# Daughter_Board.net
KiCad netlist of a schematic drawn in EAGLE
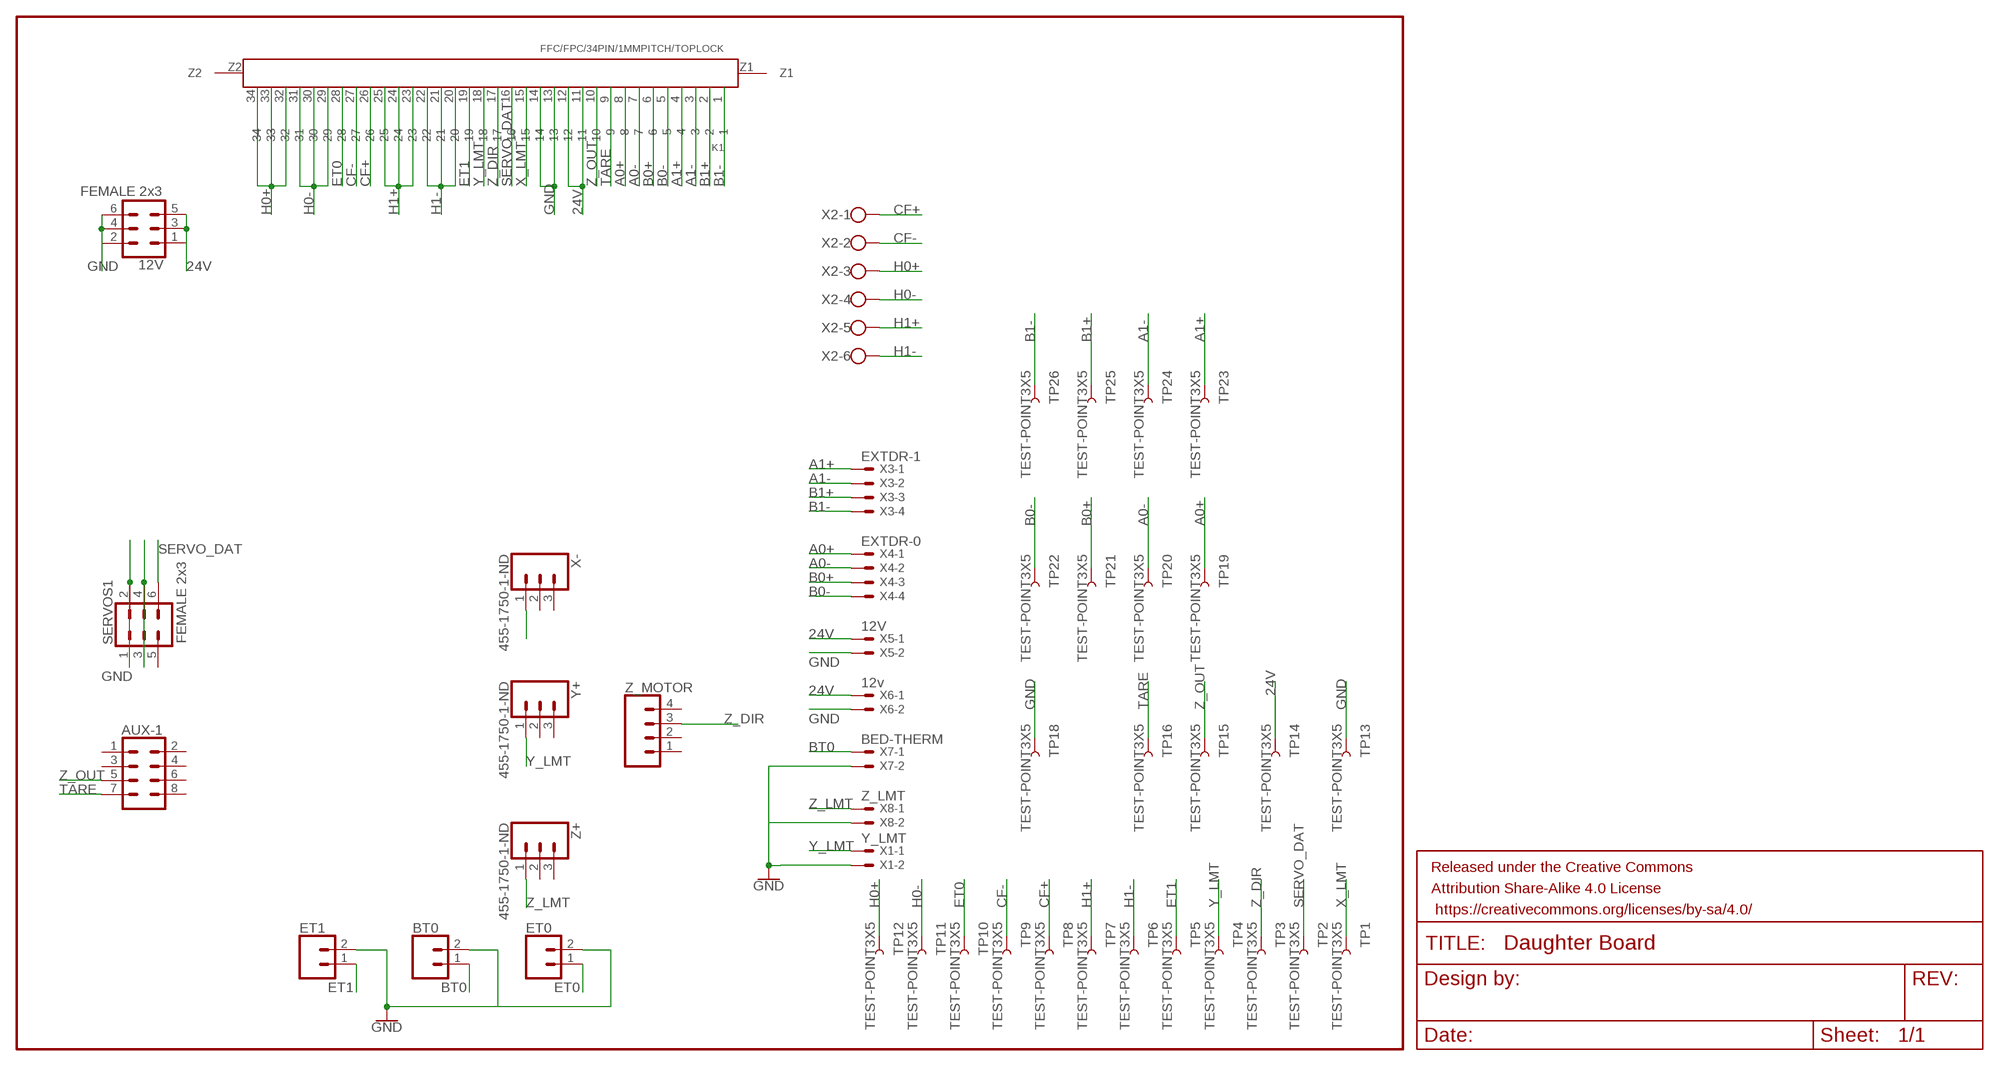
[diagram p0: schematic, sheet 1]

(export (version "E")
  (design (tool "Eeschema 10.0.6"))
  (components
    (comp (ref "12V")
      (value "FEMALE 2x3")
      (footprint "eagle-import:2X3")
      (libsource (lib "eagle-import") (part "CONN_03X2FEMALE"))
    )
    (comp (ref "AUX-1")
      (value "CONN_04X2")
      (footprint "eagle-import:2X4")
      (libsource (lib "eagle-import") (part "CONN_04X2"))
    )
    (comp (ref "BT0")
      (value "CONN_02")
      (footprint "eagle-import:1X02")
      (libsource (lib "eagle-import") (part "CONN_02"))
    )
    (comp (ref "ET0")
      (value "CONN_02")
      (footprint "eagle-import:1X02")
      (libsource (lib "eagle-import") (part "CONN_02"))
    )
    (comp (ref "ET1")
      (value "CONN_02")
      (footprint "eagle-import:1X02")
      (libsource (lib "eagle-import") (part "CONN_02"))
    )
    (comp (ref "FRAME1")
      (value "FRAME-LETTERNO_PACKAGE")
      (footprint "eagle-import:DUMMY")
      (fields (field (name "DESIGNER") "Nobody"))
      (libsource (lib "eagle-import") (part "FRAME-LETTERNO_PACKAGE"))
    )
    (comp (ref "K1")
      (value "FFC/FPC/34PIN/1MMPITCH/TOPLOCK")
      (footprint "eagle-import:34PIN_1MMPITCH_FFC_FPC")
      (libsource (lib "eagle-import") (part "FFC/FPC/34PIN/1MMPITCH/TOPLOCK"))
    )
    (comp (ref "SERVOS1")
      (value "FEMALE 2x3")
      (footprint "eagle-import:2X3")
      (libsource (lib "eagle-import") (part "CONN_03X2FEMALE"))
    )
    (comp (ref "TP1")
      (value "TEST-POINT3X5")
      (footprint "eagle-import:PAD.03X.05")
      (libsource (lib "eagle-import") (part "TEST-POINT3X5"))
    )
    (comp (ref "TP2")
      (value "TEST-POINT3X5")
      (footprint "eagle-import:PAD.03X.05")
      (libsource (lib "eagle-import") (part "TEST-POINT3X5"))
    )
    (comp (ref "TP3")
      (value "TEST-POINT3X5")
      (footprint "eagle-import:PAD.03X.05")
      (libsource (lib "eagle-import") (part "TEST-POINT3X5"))
    )
    (comp (ref "TP4")
      (value "TEST-POINT3X5")
      (footprint "eagle-import:PAD.03X.05")
      (libsource (lib "eagle-import") (part "TEST-POINT3X5"))
    )
    (comp (ref "TP5")
      (value "TEST-POINT3X5")
      (footprint "eagle-import:PAD.03X.05")
      (libsource (lib "eagle-import") (part "TEST-POINT3X5"))
    )
    (comp (ref "TP6")
      (value "TEST-POINT3X5")
      (footprint "eagle-import:PAD.03X.05")
      (libsource (lib "eagle-import") (part "TEST-POINT3X5"))
    )
    (comp (ref "TP7")
      (value "TEST-POINT3X5")
      (footprint "eagle-import:PAD.03X.05")
      (libsource (lib "eagle-import") (part "TEST-POINT3X5"))
    )
    (comp (ref "TP8")
      (value "TEST-POINT3X5")
      (footprint "eagle-import:PAD.03X.05")
      (libsource (lib "eagle-import") (part "TEST-POINT3X5"))
    )
    (comp (ref "TP9")
      (value "TEST-POINT3X5")
      (footprint "eagle-import:PAD.03X.05")
      (libsource (lib "eagle-import") (part "TEST-POINT3X5"))
    )
    (comp (ref "TP10")
      (value "TEST-POINT3X5")
      (footprint "eagle-import:PAD.03X.05")
      (libsource (lib "eagle-import") (part "TEST-POINT3X5"))
    )
    (comp (ref "TP11")
      (value "TEST-POINT3X5")
      (footprint "eagle-import:PAD.03X.05")
      (libsource (lib "eagle-import") (part "TEST-POINT3X5"))
    )
    (comp (ref "TP12")
      (value "TEST-POINT3X5")
      (footprint "eagle-import:PAD.03X.05")
      (libsource (lib "eagle-import") (part "TEST-POINT3X5"))
    )
    (comp (ref "TP13")
      (value "TEST-POINT3X5")
      (footprint "eagle-import:PAD.03X.05")
      (libsource (lib "eagle-import") (part "TEST-POINT3X5"))
    )
    (comp (ref "TP14")
      (value "TEST-POINT3X5")
      (footprint "eagle-import:PAD.03X.05")
      (libsource (lib "eagle-import") (part "TEST-POINT3X5"))
    )
    (comp (ref "TP15")
      (value "TEST-POINT3X5")
      (footprint "eagle-import:PAD.03X.05")
      (libsource (lib "eagle-import") (part "TEST-POINT3X5"))
    )
    (comp (ref "TP16")
      (value "TEST-POINT3X5")
      (footprint "eagle-import:PAD.03X.05")
      (libsource (lib "eagle-import") (part "TEST-POINT3X5"))
    )
    (comp (ref "TP18")
      (value "TEST-POINT3X5")
      (footprint "eagle-import:PAD.03X.05")
      (libsource (lib "eagle-import") (part "TEST-POINT3X5"))
    )
    (comp (ref "TP19")
      (value "TEST-POINT3X5")
      (footprint "eagle-import:PAD.03X.05")
      (libsource (lib "eagle-import") (part "TEST-POINT3X5"))
    )
    (comp (ref "TP20")
      (value "TEST-POINT3X5")
      (footprint "eagle-import:PAD.03X.05")
      (libsource (lib "eagle-import") (part "TEST-POINT3X5"))
    )
    (comp (ref "TP21")
      (value "TEST-POINT3X5")
      (footprint "eagle-import:PAD.03X.05")
      (libsource (lib "eagle-import") (part "TEST-POINT3X5"))
    )
    (comp (ref "TP22")
      (value "TEST-POINT3X5")
      (footprint "eagle-import:PAD.03X.05")
      (libsource (lib "eagle-import") (part "TEST-POINT3X5"))
    )
    (comp (ref "TP23")
      (value "TEST-POINT3X5")
      (footprint "eagle-import:PAD.03X.05")
      (libsource (lib "eagle-import") (part "TEST-POINT3X5"))
    )
    (comp (ref "TP24")
      (value "TEST-POINT3X5")
      (footprint "eagle-import:PAD.03X.05")
      (libsource (lib "eagle-import") (part "TEST-POINT3X5"))
    )
    (comp (ref "TP25")
      (value "TEST-POINT3X5")
      (footprint "eagle-import:PAD.03X.05")
      (libsource (lib "eagle-import") (part "TEST-POINT3X5"))
    )
    (comp (ref "TP26")
      (value "TEST-POINT3X5")
      (footprint "eagle-import:PAD.03X.05")
      (libsource (lib "eagle-import") (part "TEST-POINT3X5"))
    )
    (comp (ref "X-")
      (value "455-1750-1-ND")
      (footprint "eagle-import:1X03")
      (libsource (lib "eagle-import") (part "CONN_03"))
    )
    (comp (ref "X1")
      (value "Y_LMT")
      (footprint "eagle-import:JST-XH-02-PACKAGE-LONG-PAD")
      (libsource (lib "eagle-import") (part "JST-XH-02-PIN-LONG-PAD"))
    )
    (comp (ref "X2")
      (value "W237-6")
      (footprint "eagle-import:W237-6")
      (libsource (lib "eagle-import") (part "W237-6"))
    )
    (comp (ref "X3")
      (value "EXTDR-1")
      (footprint "eagle-import:JST-XH-04-PACKAGE-LONG-PAD")
      (libsource (lib "eagle-import") (part "JST-XH-04-PIN-LONG-PAD"))
    )
    (comp (ref "X4")
      (value "EXTDR-0")
      (footprint "eagle-import:JST-XH-04-PACKAGE-LONG-PAD")
      (libsource (lib "eagle-import") (part "JST-XH-04-PIN-LONG-PAD"))
    )
    (comp (ref "X5")
      (value "12V")
      (footprint "eagle-import:JST-XH-02-PACKAGE-LONG-PAD")
      (libsource (lib "eagle-import") (part "JST-XH-02-PIN-LONG-PAD"))
    )
    (comp (ref "X6")
      (value "12v")
      (footprint "eagle-import:JST-XH-02-PACKAGE-LONG-PAD")
      (libsource (lib "eagle-import") (part "JST-XH-02-PIN-LONG-PAD"))
    )
    (comp (ref "X7")
      (value "BED-THERM")
      (footprint "eagle-import:JST-XH-02-PACKAGE-LONG-PAD")
      (libsource (lib "eagle-import") (part "JST-XH-02-PIN-LONG-PAD"))
    )
    (comp (ref "X8")
      (value "Z_LMT")
      (footprint "eagle-import:JST-XH-02-PACKAGE-LONG-PAD")
      (libsource (lib "eagle-import") (part "JST-XH-02-PIN-LONG-PAD"))
    )
    (comp (ref "Y+")
      (value "455-1750-1-ND")
      (footprint "eagle-import:1X03")
      (libsource (lib "eagle-import") (part "CONN_03"))
    )
    (comp (ref "Z+")
      (value "455-1750-1-ND")
      (footprint "eagle-import:1X03")
      (libsource (lib "eagle-import") (part "CONN_03"))
    )
    (comp (ref "Z_MOTOR")
      (value "CONN_04")
      (footprint "eagle-import:1X04")
      (libsource (lib "eagle-import") (part "CONN_04"))
    )
  )
  (nets
    (net (code "1") (name "/24V") (class "Default")
      (node (ref "12V") (pin "1") (pinfunction "1_1") (pintype "bidirectional"))
      (node (ref "12V") (pin "3") (pinfunction "3_3") (pintype "bidirectional"))
      (node (ref "12V") (pin "5") (pinfunction "5_5") (pintype "bidirectional"))
      (node (ref "K1") (pin "11") (pinfunction "11_11") (pintype "bidirectional"))
      (node (ref "K1") (pin "12") (pinfunction "12_12") (pintype "bidirectional"))
      (node (ref "TP14") (pin "P$1") (pinfunction "1_P$1") (pintype "bidirectional"))
      (node (ref "X5") (pin "1") (pinfunction "S_1") (pintype "passive"))
      (node (ref "X6") (pin "1") (pinfunction "S_1") (pintype "passive"))
    )
    (net (code "2") (name "/A0+") (class "Default")
      (node (ref "K1") (pin "8") (pinfunction "8_8") (pintype "bidirectional"))
      (node (ref "TP19") (pin "P$1") (pinfunction "1_P$1") (pintype "bidirectional"))
      (node (ref "X4") (pin "1") (pinfunction "S_1") (pintype "passive"))
    )
    (net (code "3") (name "/A0-") (class "Default")
      (node (ref "K1") (pin "7") (pinfunction "7_7") (pintype "bidirectional"))
      (node (ref "TP20") (pin "P$1") (pinfunction "1_P$1") (pintype "bidirectional"))
      (node (ref "X4") (pin "2") (pinfunction "S_2") (pintype "passive"))
    )
    (net (code "4") (name "/A1+") (class "Default")
      (node (ref "K1") (pin "4") (pinfunction "4_4") (pintype "bidirectional"))
      (node (ref "TP23") (pin "P$1") (pinfunction "1_P$1") (pintype "bidirectional"))
      (node (ref "X3") (pin "1") (pinfunction "S_1") (pintype "passive"))
    )
    (net (code "5") (name "/A1-") (class "Default")
      (node (ref "K1") (pin "3") (pinfunction "3_3") (pintype "bidirectional"))
      (node (ref "TP24") (pin "P$1") (pinfunction "1_P$1") (pintype "bidirectional"))
      (node (ref "X3") (pin "2") (pinfunction "S_2") (pintype "passive"))
    )
    (net (code "6") (name "/B0+") (class "Default")
      (node (ref "K1") (pin "6") (pinfunction "6_6") (pintype "bidirectional"))
      (node (ref "TP21") (pin "P$1") (pinfunction "1_P$1") (pintype "bidirectional"))
      (node (ref "X4") (pin "3") (pinfunction "S_3") (pintype "passive"))
    )
    (net (code "7") (name "/B0-") (class "Default")
      (node (ref "K1") (pin "5") (pinfunction "5_5") (pintype "bidirectional"))
      (node (ref "TP22") (pin "P$1") (pinfunction "1_P$1") (pintype "bidirectional"))
      (node (ref "X4") (pin "4") (pinfunction "S_4") (pintype "passive"))
    )
    (net (code "8") (name "/B1+") (class "Default")
      (node (ref "K1") (pin "2") (pinfunction "2_2") (pintype "bidirectional"))
      (node (ref "TP25") (pin "P$1") (pinfunction "1_P$1") (pintype "bidirectional"))
      (node (ref "X3") (pin "3") (pinfunction "S_3") (pintype "passive"))
    )
    (net (code "9") (name "/B1-") (class "Default")
      (node (ref "K1") (pin "1") (pinfunction "1_1") (pintype "bidirectional"))
      (node (ref "TP26") (pin "P$1") (pinfunction "1_P$1") (pintype "bidirectional"))
      (node (ref "X3") (pin "4") (pinfunction "S_4") (pintype "passive"))
    )
    (net (code "10") (name "/BT0") (class "Default")
      (node (ref "BT0") (pin "1") (pinfunction "1_1") (pintype "passive"))
      (node (ref "X7") (pin "1") (pinfunction "S_1") (pintype "passive"))
    )
    (net (code "11") (name "/CF+") (class "Default")
      (node (ref "K1") (pin "26") (pinfunction "26_26") (pintype "bidirectional"))
      (node (ref "TP8") (pin "P$1") (pinfunction "1_P$1") (pintype "bidirectional"))
      (node (ref "X2") (pin "1") (pinfunction "KL_1") (pintype "passive"))
    )
    (net (code "12") (name "/CF-") (class "Default")
      (node (ref "K1") (pin "27") (pinfunction "27_27") (pintype "bidirectional"))
      (node (ref "TP9") (pin "P$1") (pinfunction "1_P$1") (pintype "bidirectional"))
      (node (ref "X2") (pin "2") (pinfunction "KL_2") (pintype "passive"))
    )
    (net (code "13") (name "/ET0") (class "Default")
      (node (ref "ET0") (pin "1") (pinfunction "1_1") (pintype "passive"))
      (node (ref "K1") (pin "28") (pinfunction "28_28") (pintype "bidirectional"))
      (node (ref "TP10") (pin "P$1") (pinfunction "1_P$1") (pintype "bidirectional"))
    )
    (net (code "14") (name "/ET1") (class "Default")
      (node (ref "ET1") (pin "1") (pinfunction "1_1") (pintype "passive"))
      (node (ref "K1") (pin "19") (pinfunction "19_19") (pintype "bidirectional"))
      (node (ref "TP5") (pin "P$1") (pinfunction "1_P$1") (pintype "bidirectional"))
    )
    (net (code "15") (name "/H0+") (class "Default")
      (node (ref "K1") (pin "32") (pinfunction "32_32") (pintype "bidirectional"))
      (node (ref "K1") (pin "33") (pinfunction "33_33") (pintype "bidirectional"))
      (node (ref "K1") (pin "34") (pinfunction "34_34") (pintype "bidirectional"))
      (node (ref "TP12") (pin "P$1") (pinfunction "1_P$1") (pintype "bidirectional"))
      (node (ref "X2") (pin "3") (pinfunction "KL_3") (pintype "passive"))
    )
    (net (code "16") (name "/H0-") (class "Default")
      (node (ref "K1") (pin "29") (pinfunction "29_29") (pintype "bidirectional"))
      (node (ref "K1") (pin "30") (pinfunction "30_30") (pintype "bidirectional"))
      (node (ref "K1") (pin "31") (pinfunction "31_31") (pintype "bidirectional"))
      (node (ref "TP11") (pin "P$1") (pinfunction "1_P$1") (pintype "bidirectional"))
      (node (ref "X2") (pin "4") (pinfunction "KL_4") (pintype "passive"))
    )
    (net (code "17") (name "/H1+") (class "Default")
      (node (ref "K1") (pin "23") (pinfunction "23_23") (pintype "bidirectional"))
      (node (ref "K1") (pin "24") (pinfunction "24_24") (pintype "bidirectional"))
      (node (ref "K1") (pin "25") (pinfunction "25_25") (pintype "bidirectional"))
      (node (ref "TP7") (pin "P$1") (pinfunction "1_P$1") (pintype "bidirectional"))
      (node (ref "X2") (pin "5") (pinfunction "KL_5") (pintype "passive"))
    )
    (net (code "18") (name "/H1-") (class "Default")
      (node (ref "K1") (pin "20") (pinfunction "20_20") (pintype "bidirectional"))
      (node (ref "K1") (pin "21") (pinfunction "21_21") (pintype "bidirectional"))
      (node (ref "K1") (pin "22") (pinfunction "22_22") (pintype "bidirectional"))
      (node (ref "TP6") (pin "P$1") (pinfunction "1_P$1") (pintype "bidirectional"))
      (node (ref "X2") (pin "6") (pinfunction "KL_6") (pintype "passive"))
    )
    (net (code "19") (name "/SERVO_DAT") (class "Default")
      (node (ref "K1") (pin "16") (pinfunction "16_16") (pintype "bidirectional"))
      (node (ref "SERVOS1") (pin "6") (pinfunction "6_6") (pintype "bidirectional"))
      (node (ref "TP2") (pin "P$1") (pinfunction "1_P$1") (pintype "bidirectional"))
    )
    (net (code "20") (name "/TARE") (class "Default")
      (node (ref "AUX-1") (pin "7") (pinfunction "7_7") (pintype "passive"))
      (node (ref "K1") (pin "9") (pinfunction "9_9") (pintype "bidirectional"))
      (node (ref "TP16") (pin "P$1") (pinfunction "1_P$1") (pintype "bidirectional"))
    )
    (net (code "21") (name "/X_LMT") (class "Default")
      (node (ref "K1") (pin "15") (pinfunction "15_15") (pintype "bidirectional"))
      (node (ref "TP1") (pin "P$1") (pinfunction "1_P$1") (pintype "bidirectional"))
      (node (ref "X-") (pin "1") (pinfunction "1_1") (pintype "passive"))
    )
    (net (code "22") (name "/Y_LMT") (class "Default")
      (node (ref "K1") (pin "18") (pinfunction "18_18") (pintype "bidirectional"))
      (node (ref "TP4") (pin "P$1") (pinfunction "1_P$1") (pintype "bidirectional"))
      (node (ref "X1") (pin "1") (pinfunction "S_1") (pintype "passive"))
      (node (ref "Y+") (pin "1") (pinfunction "1_1") (pintype "passive"))
    )
    (net (code "23") (name "/Z_DIR") (class "Default")
      (node (ref "K1") (pin "17") (pinfunction "17_17") (pintype "bidirectional"))
      (node (ref "TP3") (pin "P$1") (pinfunction "1_P$1") (pintype "bidirectional"))
      (node (ref "Z_MOTOR") (pin "3") (pinfunction "3_3") (pintype "passive"))
    )
    (net (code "24") (name "/Z_LMT") (class "Default")
      (node (ref "X8") (pin "1") (pinfunction "S_1") (pintype "passive"))
      (node (ref "Z+") (pin "1") (pinfunction "1_1") (pintype "passive"))
    )
    (net (code "25") (name "/Z_OUT") (class "Default")
      (node (ref "AUX-1") (pin "5") (pinfunction "5_5") (pintype "passive"))
      (node (ref "K1") (pin "10") (pinfunction "10_10") (pintype "bidirectional"))
      (node (ref "TP15") (pin "P$1") (pinfunction "1_P$1") (pintype "bidirectional"))
    )
    (net (code "26") (name "GND") (class "Default")
      (node (ref "12V") (pin "2") (pinfunction "2_2") (pintype "bidirectional"))
      (node (ref "12V") (pin "4") (pinfunction "4_4") (pintype "bidirectional"))
      (node (ref "12V") (pin "6") (pinfunction "6_6") (pintype "bidirectional"))
      (node (ref "BT0") (pin "2") (pinfunction "2_2") (pintype "passive"))
      (node (ref "ET0") (pin "2") (pinfunction "2_2") (pintype "passive"))
      (node (ref "ET1") (pin "2") (pinfunction "2_2") (pintype "passive"))
      (node (ref "K1") (pin "13") (pinfunction "13_13") (pintype "bidirectional"))
      (node (ref "K1") (pin "14") (pinfunction "14_14") (pintype "bidirectional"))
      (node (ref "SERVOS1") (pin "1") (pinfunction "1_1") (pintype "bidirectional"))
      (node (ref "SERVOS1") (pin "2") (pinfunction "2_2") (pintype "bidirectional"))
      (node (ref "TP13") (pin "P$1") (pinfunction "1_P$1") (pintype "bidirectional"))
      (node (ref "TP18") (pin "P$1") (pinfunction "1_P$1") (pintype "bidirectional"))
      (node (ref "X1") (pin "2") (pinfunction "S_2") (pintype "passive"))
      (node (ref "X5") (pin "2") (pinfunction "S_2") (pintype "passive"))
      (node (ref "X6") (pin "2") (pinfunction "S_2") (pintype "passive"))
      (node (ref "X7") (pin "2") (pinfunction "S_2") (pintype "passive"))
      (node (ref "X8") (pin "2") (pinfunction "S_2") (pintype "passive"))
    )
    (net (code "27") (name "Net-(SERVOS1-Pad3)") (class "Default")
      (node (ref "SERVOS1") (pin "3") (pinfunction "3_3") (pintype "bidirectional"))
      (node (ref "SERVOS1") (pin "4") (pinfunction "4_4") (pintype "bidirectional"))
    )
    (net (code "28") (name "unconnected-(AUX-1-Pad1)") (class "Default")
      (node (ref "AUX-1") (pin "1") (pinfunction "1_1") (pintype "passive"))
    )
    (net (code "29") (name "unconnected-(AUX-1-Pad2)") (class "Default")
      (node (ref "AUX-1") (pin "2") (pinfunction "2_2") (pintype "passive"))
    )
    (net (code "30") (name "unconnected-(AUX-1-Pad3)") (class "Default")
      (node (ref "AUX-1") (pin "3") (pinfunction "3_3") (pintype "passive"))
    )
    (net (code "31") (name "unconnected-(AUX-1-Pad4)") (class "Default")
      (node (ref "AUX-1") (pin "4") (pinfunction "4_4") (pintype "passive"))
    )
    (net (code "32") (name "unconnected-(AUX-1-Pad6)") (class "Default")
      (node (ref "AUX-1") (pin "6") (pinfunction "6_6") (pintype "passive"))
    )
    (net (code "33") (name "unconnected-(AUX-1-Pad8)") (class "Default")
      (node (ref "AUX-1") (pin "8") (pinfunction "8_8") (pintype "passive"))
    )
    (net (code "34") (name "unconnected-(K1-PadZ1)") (class "Default")
      (node (ref "K1") (pin "Z1") (pinfunction "Z1_Z1") (pintype "bidirectional"))
    )
    (net (code "35") (name "unconnected-(K1-PadZ2)") (class "Default")
      (node (ref "K1") (pin "Z2") (pinfunction "Z2_Z2") (pintype "bidirectional"))
    )
    (net (code "36") (name "unconnected-(SERVOS1-Pad5)") (class "Default")
      (node (ref "SERVOS1") (pin "5") (pinfunction "5_5") (pintype "bidirectional"))
    )
    (net (code "37") (name "unconnected-(X--Pad2)") (class "Default")
      (node (ref "X-") (pin "2") (pinfunction "2_2") (pintype "passive"))
    )
    (net (code "38") (name "unconnected-(X--Pad3)") (class "Default")
      (node (ref "X-") (pin "3") (pinfunction "3_3") (pintype "passive"))
    )
    (net (code "39") (name "unconnected-(Y+-Pad2)") (class "Default")
      (node (ref "Y+") (pin "2") (pinfunction "2_2") (pintype "passive"))
    )
    (net (code "40") (name "unconnected-(Y+-Pad3)") (class "Default")
      (node (ref "Y+") (pin "3") (pinfunction "3_3") (pintype "passive"))
    )
    (net (code "41") (name "unconnected-(Z+-Pad2)") (class "Default")
      (node (ref "Z+") (pin "2") (pinfunction "2_2") (pintype "passive"))
    )
    (net (code "42") (name "unconnected-(Z+-Pad3)") (class "Default")
      (node (ref "Z+") (pin "3") (pinfunction "3_3") (pintype "passive"))
    )
    (net (code "43") (name "unconnected-(Z_MOTOR-Pad1)") (class "Default")
      (node (ref "Z_MOTOR") (pin "1") (pinfunction "1_1") (pintype "passive"))
    )
    (net (code "44") (name "unconnected-(Z_MOTOR-Pad2)") (class "Default")
      (node (ref "Z_MOTOR") (pin "2") (pinfunction "2_2") (pintype "passive"))
    )
    (net (code "45") (name "unconnected-(Z_MOTOR-Pad4)") (class "Default")
      (node (ref "Z_MOTOR") (pin "4") (pinfunction "4_4") (pintype "passive"))
    )
  )
)
